# Tipper_Remote_Base_Unit.net
KiCad netlist of a schematic drawn in EAGLE
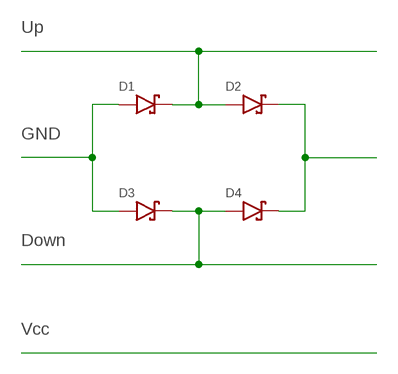
[diagram p0: schematic, sheet 1]

(export (version "E")
  (design (tool "Eeschema 10.0.6"))
  (components
    (comp (ref "D1")
      (value "DIODE-SCHOTTKY-1N5822")
      (footprint "eagle-import:DIODE_SMB")
      (libsource (lib "eagle-import") (part "DIODE-SCHOTTKY-1N5822"))
    )
    (comp (ref "D2")
      (value "DIODE-SCHOTTKY-1N5822")
      (footprint "eagle-import:DIODE_SMB")
      (libsource (lib "eagle-import") (part "DIODE-SCHOTTKY-1N5822"))
    )
    (comp (ref "D3")
      (value "DIODE-SCHOTTKY-1N5822")
      (footprint "eagle-import:DIODE_SMB")
      (libsource (lib "eagle-import") (part "DIODE-SCHOTTKY-1N5822"))
    )
    (comp (ref "D4")
      (value "DIODE-SCHOTTKY-1N5822")
      (footprint "eagle-import:DIODE_SMB")
      (libsource (lib "eagle-import") (part "DIODE-SCHOTTKY-1N5822"))
    )
  )
  (nets
    (net (code "1") (name "Net-(D1-PadA)") (class "Default")
      (node (ref "D1") (pin "A") (pinfunction "A_A") (pintype "passive"))
      (node (ref "D3") (pin "A") (pinfunction "A_A") (pintype "passive"))
    )
    (net (code "2") (name "Net-(D1-PadC)") (class "Default")
      (node (ref "D1") (pin "C") (pinfunction "C_C") (pintype "passive"))
      (node (ref "D2") (pin "A") (pinfunction "A_A") (pintype "passive"))
    )
    (net (code "3") (name "Net-(D2-PadC)") (class "Default")
      (node (ref "D2") (pin "C") (pinfunction "C_C") (pintype "passive"))
      (node (ref "D4") (pin "C") (pinfunction "C_C") (pintype "passive"))
    )
    (net (code "4") (name "Net-(D3-PadC)") (class "Default")
      (node (ref "D3") (pin "C") (pinfunction "C_C") (pintype "passive"))
      (node (ref "D4") (pin "A") (pinfunction "A_A") (pintype "passive"))
    )
  )
)
